# 19_WIFI_BLE.net
KiCad netlist of a schematic drawn in Altium Designer
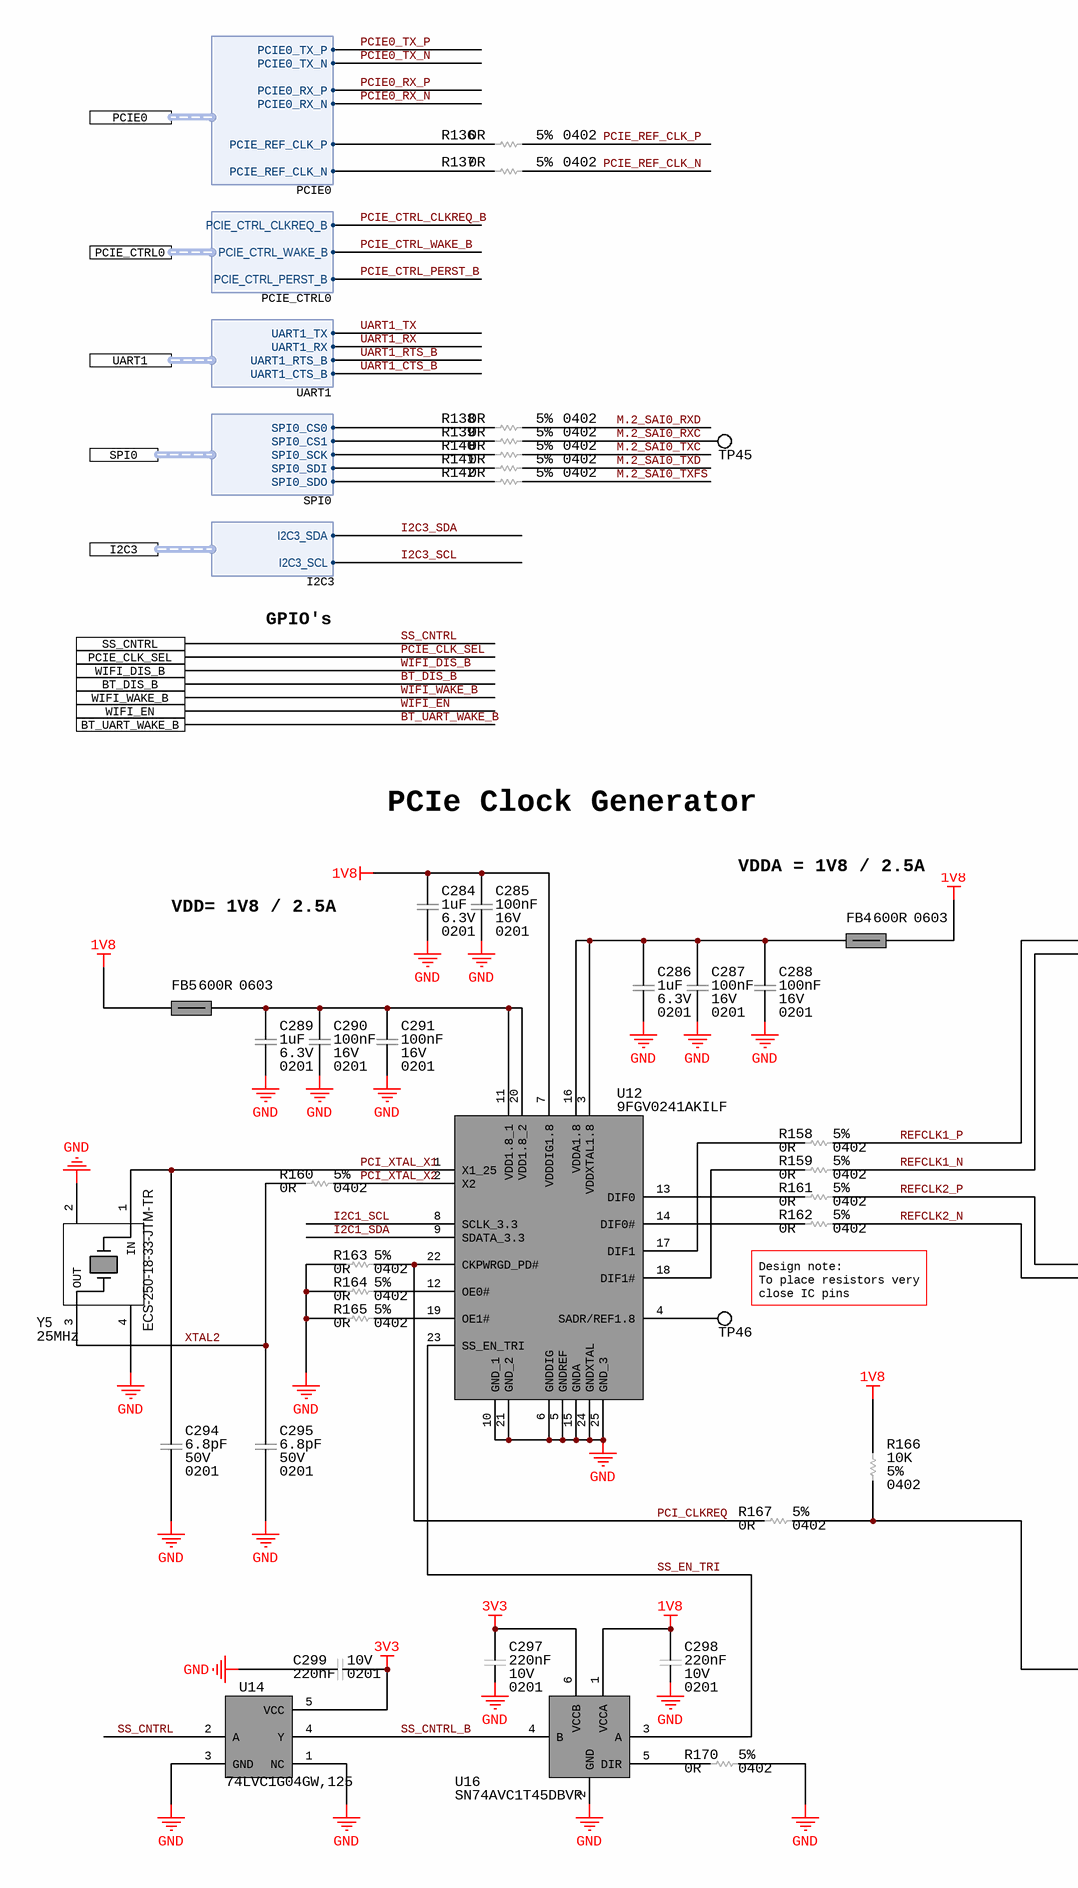
[diagram p0: 19_WIFI_BLE.SchDoc, left]
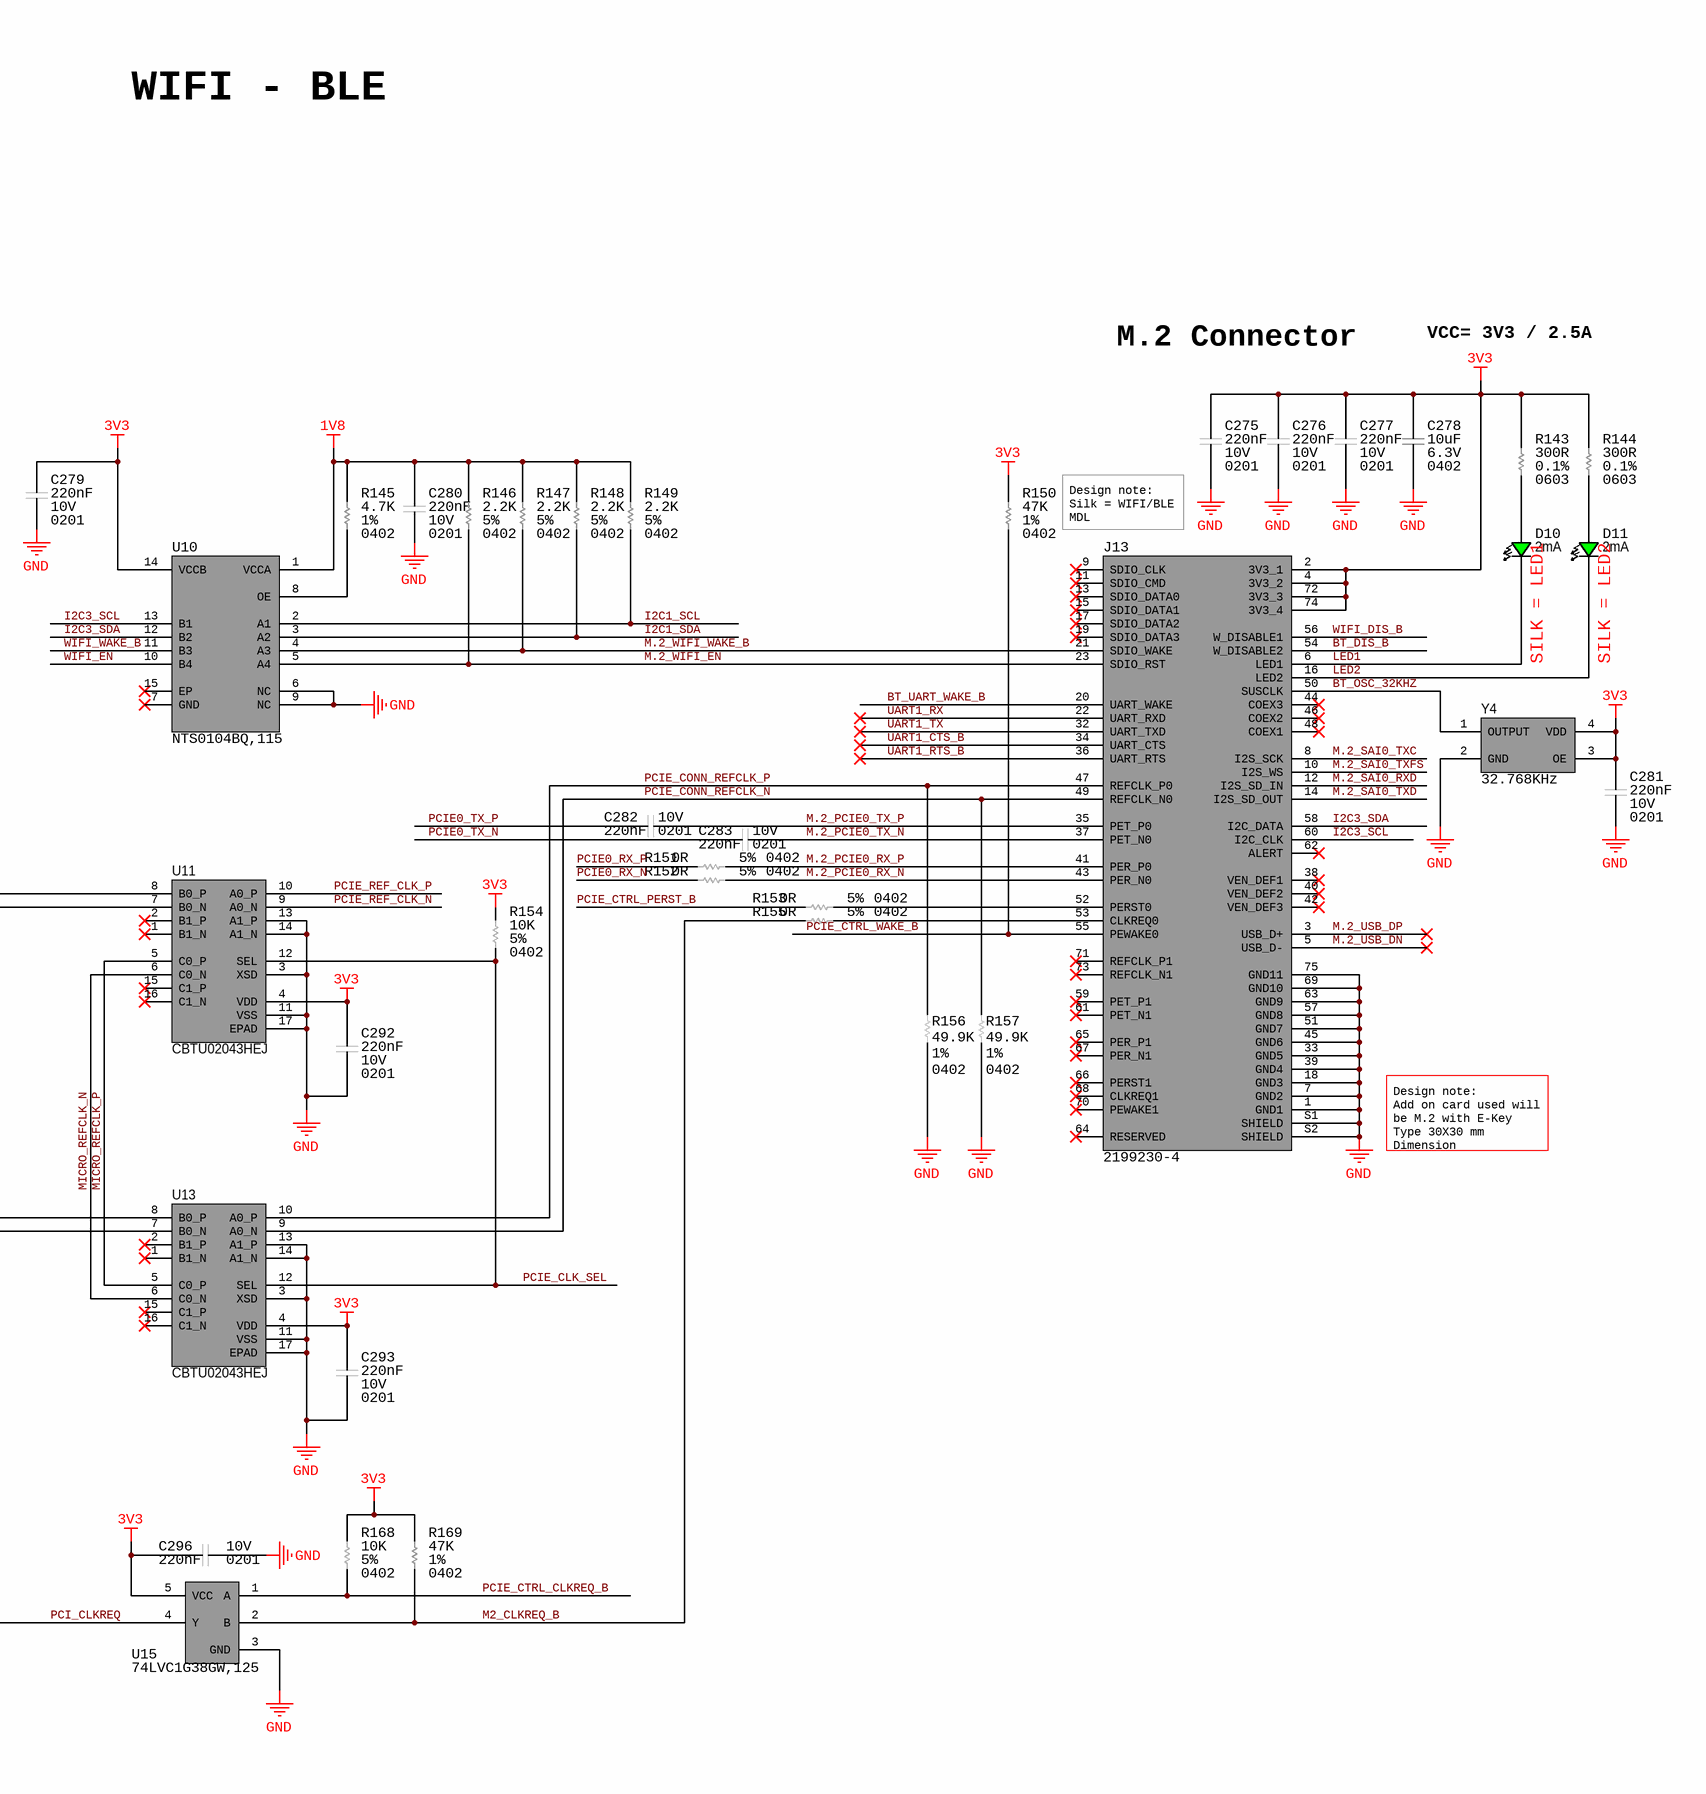
[diagram p1: 19_WIFI_BLE.SchDoc, right]

(export (version "E")
  (design (tool "Eeschema 10.0.6"))
  (components
    (comp (ref "C275")
      (value "LMK063BJ224MP-F")
      (footprint "CAP_0201_CAPC0603X03N")
      (description "Multilayer Ceramic Capacitors (High dielectric type), 10V, 0.22 uF, ± 20 %, 0201, X5R, RoHS")
      (fields
        (field (name "MANUFACTURER") "Taiyo Yuden")
        (field (name "TOLERANCE") "20%")
        (field (name "VOLTAGE RATING (DC)") "10V")
        (field (name "CAPACITANCE") "220nF")
        (field (name "CASE/PACKAGE") "0201")
      )
      (libsource (lib "Electronic Devices_LIB") (part "CAP_0.22UF_10V_X5R_0201"))
    )
    (comp (ref "C276")
      (value "LMK063BJ224MP-F")
      (footprint "CAP_0201_CAPC0603X03N")
      (description "Multilayer Ceramic Capacitors (High dielectric type), 10V, 0.22 uF, ± 20 %, 0201, X5R, RoHS")
      (fields
        (field (name "MANUFACTURER") "Taiyo Yuden")
        (field (name "TOLERANCE") "20%")
        (field (name "VOLTAGE RATING (DC)") "10V")
        (field (name "CAPACITANCE") "220nF")
        (field (name "CASE/PACKAGE") "0201")
      )
      (libsource (lib "Electronic Devices_LIB") (part "CAP_0.22UF_10V_X5R_0201"))
    )
    (comp (ref "C277")
      (value "LMK063BJ224MP-F")
      (footprint "CAP_0201_CAPC0603X03N")
      (description "Multilayer Ceramic Capacitors (High dielectric type), 10V, 0.22 uF, ± 20 %, 0201, X5R, RoHS")
      (fields
        (field (name "MANUFACTURER") "Taiyo Yuden")
        (field (name "TOLERANCE") "20%")
        (field (name "VOLTAGE RATING (DC)") "10V")
        (field (name "CAPACITANCE") "220nF")
        (field (name "CASE/PACKAGE") "0201")
      )
      (libsource (lib "Electronic Devices_LIB") (part "CAP_0.22UF_10V_X5R_0201"))
    )
    (comp (ref "C278")
      (value "CL05A106MQ5NUNC")
      (footprint "CAP_0402_CAPC1005X05N")
      (description "Cap Ceramic 10uF 6.3V X5R 20% SMD 0402 85C T/R")
      (fields
        (field (name "MANUFACTURER") "Samsung")
        (field (name "TOLERANCE") "20%")
        (field (name "CASE/PACKAGE") "0402")
        (field (name "CAPACITANCE") "10uF")
        (field (name "VOLTAGE RATING") "6.3V")
      )
      (libsource (lib "Electronic Devices_LIB") (part "CAP_10UF_6.3V_X5R_0402"))
    )
    (comp (ref "C279")
      (value "LMK063BJ224MP-F")
      (footprint "CAP_0201_CAPC0603X03N")
      (description "Multilayer Ceramic Capacitors (High dielectric type), 10V, 0.22 uF, ± 20 %, 0201, X5R, RoHS")
      (fields
        (field (name "MANUFACTURER") "Taiyo Yuden")
        (field (name "TOLERANCE") "20%")
        (field (name "VOLTAGE RATING (DC)") "10V")
        (field (name "CAPACITANCE") "220nF")
        (field (name "CASE/PACKAGE") "0201")
      )
      (libsource (lib "Electronic Devices_LIB") (part "CAP_0.22UF_10V_X5R_0201"))
    )
    (comp (ref "C280")
      (value "LMK063BJ224MP-F")
      (footprint "CAP_0201_CAPC0603X03N")
      (description "Multilayer Ceramic Capacitors (High dielectric type), 10V, 0.22 uF, ± 20 %, 0201, X5R, RoHS")
      (fields
        (field (name "MANUFACTURER") "Taiyo Yuden")
        (field (name "TOLERANCE") "20%")
        (field (name "VOLTAGE RATING (DC)") "10V")
        (field (name "CAPACITANCE") "220nF")
        (field (name "CASE/PACKAGE") "0201")
      )
      (libsource (lib "Electronic Devices_LIB") (part "CAP_0.22UF_10V_X5R_0201"))
    )
    (comp (ref "C281")
      (value "LMK063BJ224MP-F")
      (footprint "CAP_0201_CAPC0603X03N")
      (description "Multilayer Ceramic Capacitors (High dielectric type), 10V, 0.22 uF, ± 20 %, 0201, X5R, RoHS")
      (fields
        (field (name "MANUFACTURER") "Taiyo Yuden")
        (field (name "TOLERANCE") "20%")
        (field (name "VOLTAGE RATING (DC)") "10V")
        (field (name "CAPACITANCE") "220nF")
        (field (name "CASE/PACKAGE") "0201")
      )
      (libsource (lib "Electronic Devices_LIB") (part "CAP_0.22UF_10V_X5R_0201"))
    )
    (comp (ref "C282")
      (value "LMK063BJ224MP-F")
      (footprint "CAP_0201_CAPC0603X03N")
      (description "Multilayer Ceramic Capacitors (High dielectric type), 10V, 0.22 uF, ± 20 %, 0201, X5R, RoHS")
      (fields
        (field (name "MANUFACTURER") "Taiyo Yuden")
        (field (name "TOLERANCE") "20%")
        (field (name "VOLTAGE RATING (DC)") "10V")
        (field (name "CAPACITANCE") "220nF")
        (field (name "CASE/PACKAGE") "0201")
      )
      (libsource (lib "Electronic Devices_LIB") (part "CAP_0.22UF_10V_X5R_0201"))
    )
    (comp (ref "C283")
      (value "LMK063BJ224MP-F")
      (footprint "CAP_0201_CAPC0603X03N")
      (description "Multilayer Ceramic Capacitors (High dielectric type), 10V, 0.22 uF, ± 20 %, 0201, X5R, RoHS")
      (fields
        (field (name "MANUFACTURER") "Taiyo Yuden")
        (field (name "TOLERANCE") "20%")
        (field (name "VOLTAGE RATING (DC)") "10V")
        (field (name "CAPACITANCE") "220nF")
        (field (name "CASE/PACKAGE") "0201")
      )
      (libsource (lib "Electronic Devices_LIB") (part "CAP_0.22UF_10V_X5R_0201"))
    )
    (comp (ref "C284")
      (value "02016D105MAT2A")
      (footprint "CAP_0201_CAPC0603X03N")
      (description "0201 1 uF 6.3 V ±20 % Tolerance X5R Surface Mount Multilayer Ceramic Capacitor")
      (fields
        (field (name "MANUFACTURER") "Kyocera AVX")
        (field (name "TOLERANCE") "20%")
        (field (name "VOLTAGE RATING (DC)") "6.3V")
        (field (name "CAPACITANCE") "1uF")
        (field (name "CASE/PACKAGE") "0201")
      )
      (libsource (lib "Electronic Devices_LIB") (part "CAP_1UF_6.3V_X5R_0201"))
    )
    (comp (ref "C285")
      (value "GRM033C71C104KE14D")
      (footprint "CAP_0201_CAPC0603X03N")
      (description "Multilayer Ceramic Capacitor, 0.1 uF, 16 V, ± 10%, X7S, 0201 [0603 Metric]")
      (fields
        (field (name "MANUFACTURER") "Murata")
        (field (name "TOLERANCE") "10%")
        (field (name "VOLTAGE RATING") "16V")
        (field (name "CAPACITANCE") "100nF")
        (field (name "CASE/PACKAGE") "0201")
      )
      (libsource (lib "Electronic Devices_LIB") (part "CAP_100nF_16V_X7S_0201"))
    )
    (comp (ref "C286")
      (value "02016D105MAT2A")
      (footprint "CAP_0201_CAPC0603X03N")
      (description "0201 1 uF 6.3 V ±20 % Tolerance X5R Surface Mount Multilayer Ceramic Capacitor")
      (fields
        (field (name "MANUFACTURER") "Kyocera AVX")
        (field (name "TOLERANCE") "20%")
        (field (name "VOLTAGE RATING (DC)") "6.3V")
        (field (name "CAPACITANCE") "1uF")
        (field (name "CASE/PACKAGE") "0201")
      )
      (libsource (lib "Electronic Devices_LIB") (part "CAP_1UF_6.3V_X5R_0201"))
    )
    (comp (ref "C287")
      (value "GRM033C71C104KE14D")
      (footprint "CAP_0201_CAPC0603X03N")
      (description "Multilayer Ceramic Capacitor, 0.1 uF, 16 V, ± 10%, X7S, 0201 [0603 Metric]")
      (fields
        (field (name "MANUFACTURER") "Murata")
        (field (name "TOLERANCE") "10%")
        (field (name "VOLTAGE RATING") "16V")
        (field (name "CAPACITANCE") "100nF")
        (field (name "CASE/PACKAGE") "0201")
      )
      (libsource (lib "Electronic Devices_LIB") (part "CAP_100nF_16V_X7S_0201"))
    )
    (comp (ref "C288")
      (value "GRM033C71C104KE14D")
      (footprint "CAP_0201_CAPC0603X03N")
      (description "Multilayer Ceramic Capacitor, 0.1 uF, 16 V, ± 10%, X7S, 0201 [0603 Metric]")
      (fields
        (field (name "MANUFACTURER") "Murata")
        (field (name "TOLERANCE") "10%")
        (field (name "VOLTAGE RATING") "16V")
        (field (name "CAPACITANCE") "100nF")
        (field (name "CASE/PACKAGE") "0201")
      )
      (libsource (lib "Electronic Devices_LIB") (part "CAP_100nF_16V_X7S_0201"))
    )
    (comp (ref "C289")
      (value "02016D105MAT2A")
      (footprint "CAP_0201_CAPC0603X03N")
      (description "0201 1 uF 6.3 V ±20 % Tolerance X5R Surface Mount Multilayer Ceramic Capacitor")
      (fields
        (field (name "MANUFACTURER") "Kyocera AVX")
        (field (name "TOLERANCE") "20%")
        (field (name "VOLTAGE RATING (DC)") "6.3V")
        (field (name "CAPACITANCE") "1uF")
        (field (name "CASE/PACKAGE") "0201")
      )
      (libsource (lib "Electronic Devices_LIB") (part "CAP_1UF_6.3V_X5R_0201"))
    )
    (comp (ref "C290")
      (value "GRM033C71C104KE14D")
      (footprint "CAP_0201_CAPC0603X03N")
      (description "Multilayer Ceramic Capacitor, 0.1 uF, 16 V, ± 10%, X7S, 0201 [0603 Metric]")
      (fields
        (field (name "MANUFACTURER") "Murata")
        (field (name "TOLERANCE") "10%")
        (field (name "VOLTAGE RATING") "16V")
        (field (name "CAPACITANCE") "100nF")
        (field (name "CASE/PACKAGE") "0201")
      )
      (libsource (lib "Electronic Devices_LIB") (part "CAP_100nF_16V_X7S_0201"))
    )
    (comp (ref "C291")
      (value "GRM033C71C104KE14D")
      (footprint "CAP_0201_CAPC0603X03N")
      (description "Multilayer Ceramic Capacitor, 0.1 uF, 16 V, ± 10%, X7S, 0201 [0603 Metric]")
      (fields
        (field (name "MANUFACTURER") "Murata")
        (field (name "TOLERANCE") "10%")
        (field (name "VOLTAGE RATING") "16V")
        (field (name "CAPACITANCE") "100nF")
        (field (name "CASE/PACKAGE") "0201")
      )
      (libsource (lib "Electronic Devices_LIB") (part "CAP_100nF_16V_X7S_0201"))
    )
    (comp (ref "C292")
      (value "LMK063BJ224MP-F")
      (footprint "CAP_0201_CAPC0603X03N")
      (description "Multilayer Ceramic Capacitors (High dielectric type), 10V, 0.22 uF, ± 20 %, 0201, X5R, RoHS")
      (fields
        (field (name "MANUFACTURER") "Taiyo Yuden")
        (field (name "TOLERANCE") "20%")
        (field (name "VOLTAGE RATING (DC)") "10V")
        (field (name "CAPACITANCE") "220nF")
        (field (name "CASE/PACKAGE") "0201")
      )
      (libsource (lib "Electronic Devices_LIB") (part "CAP_0.22UF_10V_X5R_0201"))
    )
    (comp (ref "C293")
      (value "LMK063BJ224MP-F")
      (footprint "CAP_0201_CAPC0603X03N")
      (description "Multilayer Ceramic Capacitors (High dielectric type), 10V, 0.22 uF, ± 20 %, 0201, X5R, RoHS")
      (fields
        (field (name "MANUFACTURER") "Taiyo Yuden")
        (field (name "TOLERANCE") "20%")
        (field (name "VOLTAGE RATING (DC)") "10V")
        (field (name "CAPACITANCE") "220nF")
        (field (name "CASE/PACKAGE") "0201")
      )
      (libsource (lib "Electronic Devices_LIB") (part "CAP_0.22UF_10V_X5R_0201"))
    )
    (comp (ref "C294")
      (value "GRM0335C1H6R8BA01D")
      (footprint "CAP_0201_CAPC0603X03N")
      (description "Cap Ceramic 6.8pF 50V C0G 0.1pF Pad SMD 0201 125C T/R")
      (fields
        (field (name "MANUFACTURER") "Murata")
        (field (name "CAPACITANCE") "6.8pF")
        (field (name "VOLTAGE RATING") "50V")
        (field (name "CASE/PACKAGE") "0201")
      )
      (libsource (lib "Electronic Devices_LIB") (part "CAP_6.8pF_50V_NP0_0201"))
    )
    (comp (ref "C295")
      (value "GRM0335C1H6R8BA01D")
      (footprint "CAP_0201_CAPC0603X03N")
      (description "Cap Ceramic 6.8pF 50V C0G 0.1pF Pad SMD 0201 125C T/R")
      (fields
        (field (name "MANUFACTURER") "Murata")
        (field (name "CAPACITANCE") "6.8pF")
        (field (name "VOLTAGE RATING") "50V")
        (field (name "CASE/PACKAGE") "0201")
      )
      (libsource (lib "Electronic Devices_LIB") (part "CAP_6.8pF_50V_NP0_0201"))
    )
    (comp (ref "C296")
      (value "LMK063BJ224MP-F")
      (footprint "CAP_0201_CAPC0603X03N")
      (description "Multilayer Ceramic Capacitors (High dielectric type), 10V, 0.22 uF, ± 20 %, 0201, X5R, RoHS")
      (fields
        (field (name "MANUFACTURER") "Taiyo Yuden")
        (field (name "TOLERANCE") "20%")
        (field (name "VOLTAGE RATING (DC)") "10V")
        (field (name "CAPACITANCE") "220nF")
        (field (name "CASE/PACKAGE") "0201")
      )
      (libsource (lib "Electronic Devices_LIB") (part "CAP_0.22UF_10V_X5R_0201"))
    )
    (comp (ref "C297")
      (value "LMK063BJ224MP-F")
      (footprint "CAP_0201_CAPC0603X03N")
      (description "Multilayer Ceramic Capacitors (High dielectric type), 10V, 0.22 uF, ± 20 %, 0201, X5R, RoHS")
      (fields
        (field (name "MANUFACTURER") "Taiyo Yuden")
        (field (name "TOLERANCE") "20%")
        (field (name "VOLTAGE RATING (DC)") "10V")
        (field (name "CAPACITANCE") "220nF")
        (field (name "CASE/PACKAGE") "0201")
      )
      (libsource (lib "Electronic Devices_LIB") (part "CAP_0.22UF_10V_X5R_0201"))
    )
    (comp (ref "C298")
      (value "LMK063BJ224MP-F")
      (footprint "CAP_0201_CAPC0603X03N")
      (description "Multilayer Ceramic Capacitors (High dielectric type), 10V, 0.22 uF, ± 20 %, 0201, X5R, RoHS")
      (fields
        (field (name "MANUFACTURER") "Taiyo Yuden")
        (field (name "TOLERANCE") "20%")
        (field (name "VOLTAGE RATING (DC)") "10V")
        (field (name "CAPACITANCE") "220nF")
        (field (name "CASE/PACKAGE") "0201")
      )
      (libsource (lib "Electronic Devices_LIB") (part "CAP_0.22UF_10V_X5R_0201"))
    )
    (comp (ref "C299")
      (value "LMK063BJ224MP-F")
      (footprint "CAP_0201_CAPC0603X03N")
      (description "Multilayer Ceramic Capacitors (High dielectric type), 10V, 0.22 uF, ± 20 %, 0201, X5R, RoHS")
      (fields
        (field (name "MANUFACTURER") "Taiyo Yuden")
        (field (name "TOLERANCE") "20%")
        (field (name "VOLTAGE RATING (DC)") "10V")
        (field (name "CAPACITANCE") "220nF")
        (field (name "CASE/PACKAGE") "0201")
      )
      (libsource (lib "Electronic Devices_LIB") (part "CAP_0.22UF_10V_X5R_0201"))
    )
    (comp (ref "D10")
      (value "APDA3020LZGCK")
      (footprint "LED_GREEN_APDA3020LZGCK")
      (description "LED GREEN CLEAR 2SMD R/A  1500mcd")
      (fields (field (name "MANUFACTURER") "Kingbright") (field (name "TEST CURRENT") "2mA"))
      (libsource (lib "Electronic Devices_LIB") (part "LED_DIO_GREEN_2mA_APDA3020LZGCK"))
    )
    (comp (ref "D11")
      (value "APDA3020LZGCK")
      (footprint "LED_GREEN_APDA3020LZGCK")
      (description "LED GREEN CLEAR 2SMD R/A  1500mcd")
      (fields (field (name "MANUFACTURER") "Kingbright") (field (name "TEST CURRENT") "2mA"))
      (libsource (lib "Electronic Devices_LIB") (part "LED_DIO_GREEN_2mA_APDA3020LZGCK"))
    )
    (comp (ref "FB4")
      (value "742792653")
      (footprint "IND_0603_INDC1608X08N")
      (description "Chip NTC Thermistors (Sensor), Resistance (at 25°C)=10kΩ, Resistance Tolerance (at 25°C)=±1%")
      (fields
        (field (name "MANUFACTURER") "Wurth Electronics")
        (field (name "TOLERANCE") "25%")
        (field (name "IMPEDANCE") "600R")
        (field (name "CASE CODE (IMPERIAL)") "0603")
      )
      (libsource (lib "Electronic Devices_LIB") (part "IND_FERRITE_BEADS_600R_300mA_0603_742792653"))
    )
    (comp (ref "FB5")
      (value "742792653")
      (footprint "IND_0603_INDC1608X08N")
      (description "Chip NTC Thermistors (Sensor), Resistance (at 25°C)=10kΩ, Resistance Tolerance (at 25°C)=±1%")
      (fields
        (field (name "MANUFACTURER") "Wurth Electronics")
        (field (name "TOLERANCE") "25%")
        (field (name "IMPEDANCE") "600R")
        (field (name "CASE CODE (IMPERIAL)") "0603")
      )
      (libsource (lib "Electronic Devices_LIB") (part "IND_FERRITE_BEADS_600R_300mA_0603_742792653"))
    )
    (comp (ref "J13")
      (value "2199230-4")
      (footprint "TE_21992304")
      (description "CONNECTOR, BACKPLANE, HOUSING, RCPT, 67POS, 2ROW; Connector Type: Card Edge; Seri")
      (fields (field (name "MANUFACTURER") "TE Connectivity"))
      (libsource (lib "Electronic Devices_LIB") (part "CONN_M.2_FEMALE_2199230-4"))
    )
    (comp (ref "R136")
      (value "ERJ-2GE0R00X")
      (footprint "RES_0402_RESC1005X04N")
      (description "SMD Chip Resistor, Jumper, 0 ohm, 100 mW, 0402 [1005 Metric], Thick Film, General Purpose")
      (fields
        (field (name "MANUFACTURER") "Panasonic")
        (field (name "CASE CODE (IMPERIAL)") "0402")
        (field (name "TOLERANCE") "5%")
        (field (name "RESISTANCE") "0R")
      )
      (libsource (lib "Electronic Devices_LIB") (part "RES_0R_5%_100mW_0402"))
    )
    (comp (ref "R137")
      (value "ERJ-2GE0R00X")
      (footprint "RES_0402_RESC1005X04N")
      (description "SMD Chip Resistor, Jumper, 0 ohm, 100 mW, 0402 [1005 Metric], Thick Film, General Purpose")
      (fields
        (field (name "MANUFACTURER") "Panasonic")
        (field (name "CASE CODE (IMPERIAL)") "0402")
        (field (name "TOLERANCE") "5%")
        (field (name "RESISTANCE") "0R")
      )
      (libsource (lib "Electronic Devices_LIB") (part "RES_0R_5%_100mW_0402"))
    )
    (comp (ref "R138")
      (value "ERJ-2GE0R00X")
      (footprint "RES_0402_RESC1005X04N")
      (description "SMD Chip Resistor, Jumper, 0 ohm, 100 mW, 0402 [1005 Metric], Thick Film, General Purpose")
      (fields
        (field (name "MANUFACTURER") "Panasonic")
        (field (name "CASE CODE (IMPERIAL)") "0402")
        (field (name "TOLERANCE") "5%")
        (field (name "RESISTANCE") "0R")
      )
      (libsource (lib "Electronic Devices_LIB") (part "RES_0R_5%_100mW_0402"))
    )
    (comp (ref "R139")
      (value "ERJ-2GE0R00X")
      (footprint "RES_0402_RESC1005X04N")
      (description "SMD Chip Resistor, Jumper, 0 ohm, 100 mW, 0402 [1005 Metric], Thick Film, General Purpose")
      (fields
        (field (name "MANUFACTURER") "Panasonic")
        (field (name "CASE CODE (IMPERIAL)") "0402")
        (field (name "TOLERANCE") "5%")
        (field (name "RESISTANCE") "0R")
      )
      (libsource (lib "Electronic Devices_LIB") (part "RES_0R_5%_100mW_0402"))
    )
    (comp (ref "R140")
      (value "ERJ-2GE0R00X")
      (footprint "RES_0402_RESC1005X04N")
      (description "SMD Chip Resistor, Jumper, 0 ohm, 100 mW, 0402 [1005 Metric], Thick Film, General Purpose")
      (fields
        (field (name "MANUFACTURER") "Panasonic")
        (field (name "CASE CODE (IMPERIAL)") "0402")
        (field (name "TOLERANCE") "5%")
        (field (name "RESISTANCE") "0R")
      )
      (libsource (lib "Electronic Devices_LIB") (part "RES_0R_5%_100mW_0402"))
    )
    (comp (ref "R141")
      (value "ERJ-2GE0R00X")
      (footprint "RES_0402_RESC1005X04N")
      (description "SMD Chip Resistor, Jumper, 0 ohm, 100 mW, 0402 [1005 Metric], Thick Film, General Purpose")
      (fields
        (field (name "MANUFACTURER") "Panasonic")
        (field (name "CASE CODE (IMPERIAL)") "0402")
        (field (name "TOLERANCE") "5%")
        (field (name "RESISTANCE") "0R")
      )
      (libsource (lib "Electronic Devices_LIB") (part "RES_0R_5%_100mW_0402"))
    )
    (comp (ref "R142")
      (value "ERJ-2GE0R00X")
      (footprint "RES_0402_RESC1005X04N")
      (description "SMD Chip Resistor, Jumper, 0 ohm, 100 mW, 0402 [1005 Metric], Thick Film, General Purpose")
      (fields
        (field (name "MANUFACTURER") "Panasonic")
        (field (name "CASE CODE (IMPERIAL)") "0402")
        (field (name "TOLERANCE") "5%")
        (field (name "RESISTANCE") "0R")
      )
      (libsource (lib "Electronic Devices_LIB") (part "RES_0R_5%_100mW_0402"))
    )
    (comp (ref "R143")
      (value "RT0603BRD07300RL")
      (footprint "RES_0603_RESC1608X04N")
      (description "Res Thin Film 0603 300 Ohm 0.1% 0.1W(1/10W) ±25ppm/C Pad SMD T/R")
      (fields
        (field (name "MANUFACTURER") "Yageo")
        (field (name "CASE CODE (IMPERIAL)") "0603")
        (field (name "TOLERANCE") "0.1%")
        (field (name "RESISTANCE") "300R")
      )
      (libsource (lib "Electronic Devices_LIB") (part "RES_300R_0.1%_100mW_0603"))
    )
    (comp (ref "R144")
      (value "RT0603BRD07300RL")
      (footprint "RES_0603_RESC1608X04N")
      (description "Res Thin Film 0603 300 Ohm 0.1% 0.1W(1/10W) ±25ppm/C Pad SMD T/R")
      (fields
        (field (name "MANUFACTURER") "Yageo")
        (field (name "CASE CODE (IMPERIAL)") "0603")
        (field (name "TOLERANCE") "0.1%")
        (field (name "RESISTANCE") "300R")
      )
      (libsource (lib "Electronic Devices_LIB") (part "RES_300R_0.1%_100mW_0603"))
    )
    (comp (ref "R145")
      (value "ERJ-2RKF4701X")
      (footprint "RES_0402_RESC1005X04N")
      (description "Res Thick Film 0402 4.7K Ohm 1% 0.1W ±100ppm/°C Molded SMD Punched Carrier T/R")
      (fields
        (field (name "MANUFACTURER") "Panasonic")
        (field (name "TOLERANCE") "1%")
        (field (name "CASE CODE (IMPERIAL)") "0402")
        (field (name "RESISTANCE") "4.7K")
      )
      (libsource (lib "Electronic Devices_LIB") (part "RES_4.7K_1%_100mW_0402"))
    )
    (comp (ref "R146")
      (value "RC0402JR-072K2L")
      (footprint "RES_0402_RESC1005X04N")
      (description "SMD Chip Resistor, 2.2 kOhm, ± 5%, 63 mW, 0402 [1005 Metric], Thick Film, General Purpose")
      (fields
        (field (name "MANUFACTURER") "Yageo")
        (field (name "TOLERANCE") "5%")
        (field (name "RESISTANCE") "2.2K")
        (field (name "CASE/PACKAGE") "0402")
      )
      (libsource (lib "Electronic Devices_LIB") (part "RES_2.2K_5%_63mW_0402"))
    )
    (comp (ref "R147")
      (value "RC0402JR-072K2L")
      (footprint "RES_0402_RESC1005X04N")
      (description "SMD Chip Resistor, 2.2 kOhm, ± 5%, 63 mW, 0402 [1005 Metric], Thick Film, General Purpose")
      (fields
        (field (name "MANUFACTURER") "Yageo")
        (field (name "TOLERANCE") "5%")
        (field (name "RESISTANCE") "2.2K")
        (field (name "CASE/PACKAGE") "0402")
      )
      (libsource (lib "Electronic Devices_LIB") (part "RES_2.2K_5%_63mW_0402"))
    )
    (comp (ref "R148")
      (value "RC0402JR-072K2L")
      (footprint "RES_0402_RESC1005X04N")
      (description "SMD Chip Resistor, 2.2 kOhm, ± 5%, 63 mW, 0402 [1005 Metric], Thick Film, General Purpose")
      (fields
        (field (name "MANUFACTURER") "Yageo")
        (field (name "TOLERANCE") "5%")
        (field (name "RESISTANCE") "2.2K")
        (field (name "CASE/PACKAGE") "0402")
      )
      (libsource (lib "Electronic Devices_LIB") (part "RES_2.2K_5%_63mW_0402"))
    )
    (comp (ref "R149")
      (value "RC0402JR-072K2L")
      (footprint "RES_0402_RESC1005X04N")
      (description "SMD Chip Resistor, 2.2 kOhm, ± 5%, 63 mW, 0402 [1005 Metric], Thick Film, General Purpose")
      (fields
        (field (name "MANUFACTURER") "Yageo")
        (field (name "TOLERANCE") "5%")
        (field (name "RESISTANCE") "2.2K")
        (field (name "CASE/PACKAGE") "0402")
      )
      (libsource (lib "Electronic Devices_LIB") (part "RES_2.2K_5%_63mW_0402"))
    )
    (comp (ref "R150")
      (value "ERJ-2RKF4702X")
      (footprint "RES_0402_RESC1005X04N")
      (description "Res Thick Film 0402 47K Ohm 1% 0.1W ±100ppm/°C Molded SMD Punched Carrier T/R")
      (fields
        (field (name "MANUFACTURER") "Panasonic")
        (field (name "TOLERANCE") "1%")
        (field (name "RESISTANCE") "47K")
        (field (name "CASE/PACKAGE") "0402")
      )
      (libsource (lib "Electronic Devices_LIB") (part "RES_47K_1%_100MW_0402"))
    )
    (comp (ref "R151")
      (value "ERJ-2GE0R00X")
      (footprint "RES_0402_RESC1005X04N")
      (description "SMD Chip Resistor, Jumper, 0 ohm, 100 mW, 0402 [1005 Metric], Thick Film, General Purpose")
      (fields
        (field (name "MANUFACTURER") "Panasonic")
        (field (name "CASE CODE (IMPERIAL)") "0402")
        (field (name "TOLERANCE") "5%")
        (field (name "RESISTANCE") "0R")
      )
      (libsource (lib "Electronic Devices_LIB") (part "RES_0R_5%_100mW_0402"))
    )
    (comp (ref "R152")
      (value "ERJ-2GE0R00X")
      (footprint "RES_0402_RESC1005X04N")
      (description "SMD Chip Resistor, Jumper, 0 ohm, 100 mW, 0402 [1005 Metric], Thick Film, General Purpose")
      (fields
        (field (name "MANUFACTURER") "Panasonic")
        (field (name "CASE CODE (IMPERIAL)") "0402")
        (field (name "TOLERANCE") "5%")
        (field (name "RESISTANCE") "0R")
      )
      (libsource (lib "Electronic Devices_LIB") (part "RES_0R_5%_100mW_0402"))
    )
    (comp (ref "R153")
      (value "ERJ-2GE0R00X")
      (footprint "RES_0402_RESC1005X04N")
      (description "SMD Chip Resistor, Jumper, 0 ohm, 100 mW, 0402 [1005 Metric], Thick Film, General Purpose")
      (fields
        (field (name "MANUFACTURER") "Panasonic")
        (field (name "CASE CODE (IMPERIAL)") "0402")
        (field (name "TOLERANCE") "5%")
        (field (name "RESISTANCE") "0R")
      )
      (libsource (lib "Electronic Devices_LIB") (part "RES_0R_5%_100mW_0402"))
    )
    (comp (ref "R154")
      (value "ERJ-2GEJ103X")
      (footprint "RES_0402_RESC1005X04N")
      (description "Res Thick Film 0402 10K Ohm 5% 1/10W ±200ppm/°C Molded SMD Punched Carrier T/R")
      (fields
        (field (name "MANUFACTURER") "Panasonic")
        (field (name "TOLERANCE") "5%")
        (field (name "RESISTANCE") "10K")
        (field (name "CASE/PACKAGE") "0402")
      )
      (libsource (lib "Electronic Devices_LIB") (part "RES_10K_5%_100mW_0402"))
    )
    (comp (ref "R155")
      (value "ERJ-2GE0R00X")
      (footprint "RES_0402_RESC1005X04N")
      (description "SMD Chip Resistor, Jumper, 0 ohm, 100 mW, 0402 [1005 Metric], Thick Film, General Purpose")
      (fields
        (field (name "MANUFACTURER") "Panasonic")
        (field (name "CASE CODE (IMPERIAL)") "0402")
        (field (name "TOLERANCE") "5%")
        (field (name "RESISTANCE") "0R")
      )
      (libsource (lib "Electronic Devices_LIB") (part "RES_0R_5%_100mW_0402"))
    )
    (comp (ref "R156")
      (value "CRCW040249K9FKED")
      (footprint "RES_0402_RESC1005X04N")
      (description "Res Thick Film 0402 49.9K Ohm 1% 1/16W ±100ppm/°C Molded SMD SMD Paper T/R")
      (fields
        (field (name "MANUFACTURER") "Vishay")
        (field (name "RESISTANCE") "49.9K")
        (field (name "TOLERANCE") "1%")
        (field (name "CASE/PACKAGE") "0402")
      )
      (libsource (lib "Electronic Devices_LIB") (part "RES_49.9K_1%_0.0625W_0402"))
    )
    (comp (ref "R157")
      (value "CRCW040249K9FKED")
      (footprint "RES_0402_RESC1005X04N")
      (description "Res Thick Film 0402 49.9K Ohm 1% 1/16W ±100ppm/°C Molded SMD SMD Paper T/R")
      (fields
        (field (name "MANUFACTURER") "Vishay")
        (field (name "RESISTANCE") "49.9K")
        (field (name "TOLERANCE") "1%")
        (field (name "CASE/PACKAGE") "0402")
      )
      (libsource (lib "Electronic Devices_LIB") (part "RES_49.9K_1%_0.0625W_0402"))
    )
    (comp (ref "R158")
      (value "ERJ-2GE0R00X")
      (footprint "RES_0402_RESC1005X04N")
      (description "SMD Chip Resistor, Jumper, 0 ohm, 100 mW, 0402 [1005 Metric], Thick Film, General Purpose")
      (fields
        (field (name "MANUFACTURER") "Panasonic")
        (field (name "CASE CODE (IMPERIAL)") "0402")
        (field (name "TOLERANCE") "5%")
        (field (name "RESISTANCE") "0R")
      )
      (libsource (lib "Electronic Devices_LIB") (part "RES_0R_5%_100mW_0402"))
    )
    (comp (ref "R159")
      (value "ERJ-2GE0R00X")
      (footprint "RES_0402_RESC1005X04N")
      (description "SMD Chip Resistor, Jumper, 0 ohm, 100 mW, 0402 [1005 Metric], Thick Film, General Purpose")
      (fields
        (field (name "MANUFACTURER") "Panasonic")
        (field (name "CASE CODE (IMPERIAL)") "0402")
        (field (name "TOLERANCE") "5%")
        (field (name "RESISTANCE") "0R")
      )
      (libsource (lib "Electronic Devices_LIB") (part "RES_0R_5%_100mW_0402"))
    )
    (comp (ref "R160")
      (value "ERJ-2GE0R00X")
      (footprint "RES_0402_RESC1005X04N")
      (description "SMD Chip Resistor, Jumper, 0 ohm, 100 mW, 0402 [1005 Metric], Thick Film, General Purpose")
      (fields
        (field (name "MANUFACTURER") "Panasonic")
        (field (name "CASE CODE (IMPERIAL)") "0402")
        (field (name "TOLERANCE") "5%")
        (field (name "RESISTANCE") "0R")
      )
      (libsource (lib "Electronic Devices_LIB") (part "RES_0R_5%_100mW_0402"))
    )
    (comp (ref "R161")
      (value "ERJ-2GE0R00X")
      (footprint "RES_0402_RESC1005X04N")
      (description "SMD Chip Resistor, Jumper, 0 ohm, 100 mW, 0402 [1005 Metric], Thick Film, General Purpose")
      (fields
        (field (name "MANUFACTURER") "Panasonic")
        (field (name "CASE CODE (IMPERIAL)") "0402")
        (field (name "TOLERANCE") "5%")
        (field (name "RESISTANCE") "0R")
      )
      (libsource (lib "Electronic Devices_LIB") (part "RES_0R_5%_100mW_0402"))
    )
    (comp (ref "R162")
      (value "ERJ-2GE0R00X")
      (footprint "RES_0402_RESC1005X04N")
      (description "SMD Chip Resistor, Jumper, 0 ohm, 100 mW, 0402 [1005 Metric], Thick Film, General Purpose")
      (fields
        (field (name "MANUFACTURER") "Panasonic")
        (field (name "CASE CODE (IMPERIAL)") "0402")
        (field (name "TOLERANCE") "5%")
        (field (name "RESISTANCE") "0R")
      )
      (libsource (lib "Electronic Devices_LIB") (part "RES_0R_5%_100mW_0402"))
    )
    (comp (ref "R163")
      (value "ERJ-2GE0R00X")
      (footprint "RES_0402_RESC1005X04N")
      (description "SMD Chip Resistor, Jumper, 0 ohm, 100 mW, 0402 [1005 Metric], Thick Film, General Purpose")
      (fields
        (field (name "MANUFACTURER") "Panasonic")
        (field (name "CASE CODE (IMPERIAL)") "0402")
        (field (name "TOLERANCE") "5%")
        (field (name "RESISTANCE") "0R")
      )
      (libsource (lib "Electronic Devices_LIB") (part "RES_0R_5%_100mW_0402"))
    )
    (comp (ref "R164")
      (value "ERJ-2GE0R00X")
      (footprint "RES_0402_RESC1005X04N")
      (description "SMD Chip Resistor, Jumper, 0 ohm, 100 mW, 0402 [1005 Metric], Thick Film, General Purpose")
      (fields
        (field (name "MANUFACTURER") "Panasonic")
        (field (name "CASE CODE (IMPERIAL)") "0402")
        (field (name "TOLERANCE") "5%")
        (field (name "RESISTANCE") "0R")
      )
      (libsource (lib "Electronic Devices_LIB") (part "RES_0R_5%_100mW_0402"))
    )
    (comp (ref "R165")
      (value "ERJ-2GE0R00X")
      (footprint "RES_0402_RESC1005X04N")
      (description "SMD Chip Resistor, Jumper, 0 ohm, 100 mW, 0402 [1005 Metric], Thick Film, General Purpose")
      (fields
        (field (name "MANUFACTURER") "Panasonic")
        (field (name "CASE CODE (IMPERIAL)") "0402")
        (field (name "TOLERANCE") "5%")
        (field (name "RESISTANCE") "0R")
      )
      (libsource (lib "Electronic Devices_LIB") (part "RES_0R_5%_100mW_0402"))
    )
    (comp (ref "R166")
      (value "ERJ-2GEJ103X")
      (footprint "RES_0402_RESC1005X04N")
      (description "Res Thick Film 0402 10K Ohm 5% 1/10W ±200ppm/°C Molded SMD Punched Carrier T/R")
      (fields
        (field (name "MANUFACTURER") "Panasonic")
        (field (name "TOLERANCE") "5%")
        (field (name "RESISTANCE") "10K")
        (field (name "CASE/PACKAGE") "0402")
      )
      (libsource (lib "Electronic Devices_LIB") (part "RES_10K_5%_100mW_0402"))
    )
    (comp (ref "R167")
      (value "ERJ-2GE0R00X")
      (footprint "RES_0402_RESC1005X04N")
      (description "SMD Chip Resistor, Jumper, 0 ohm, 100 mW, 0402 [1005 Metric], Thick Film, General Purpose")
      (fields
        (field (name "MANUFACTURER") "Panasonic")
        (field (name "CASE CODE (IMPERIAL)") "0402")
        (field (name "TOLERANCE") "5%")
        (field (name "RESISTANCE") "0R")
      )
      (libsource (lib "Electronic Devices_LIB") (part "RES_0R_5%_100mW_0402"))
    )
    (comp (ref "R168")
      (value "ERJ-2GEJ103X")
      (footprint "RES_0402_RESC1005X04N")
      (description "Res Thick Film 0402 10K Ohm 5% 1/10W ±200ppm/°C Molded SMD Punched Carrier T/R")
      (fields
        (field (name "MANUFACTURER") "Panasonic")
        (field (name "TOLERANCE") "5%")
        (field (name "RESISTANCE") "10K")
        (field (name "CASE/PACKAGE") "0402")
      )
      (libsource (lib "Electronic Devices_LIB") (part "RES_10K_5%_100mW_0402"))
    )
    (comp (ref "R169")
      (value "ERJ-2RKF4702X")
      (footprint "RES_0402_RESC1005X04N")
      (description "Res Thick Film 0402 47K Ohm 1% 0.1W ±100ppm/°C Molded SMD Punched Carrier T/R")
      (fields
        (field (name "MANUFACTURER") "Panasonic")
        (field (name "TOLERANCE") "1%")
        (field (name "RESISTANCE") "47K")
        (field (name "CASE/PACKAGE") "0402")
      )
      (libsource (lib "Electronic Devices_LIB") (part "RES_47K_1%_100MW_0402"))
    )
    (comp (ref "R170")
      (value "ERJ-2GE0R00X")
      (footprint "RES_0402_RESC1005X04N")
      (description "SMD Chip Resistor, Jumper, 0 ohm, 100 mW, 0402 [1005 Metric], Thick Film, General Purpose")
      (fields
        (field (name "MANUFACTURER") "Panasonic")
        (field (name "CASE CODE (IMPERIAL)") "0402")
        (field (name "TOLERANCE") "5%")
        (field (name "RESISTANCE") "0R")
      )
      (libsource (lib "Electronic Devices_LIB") (part "RES_0R_5%_100mW_0402"))
    )
    (comp (ref "TP45")
      (value "NO COMPONENT")
      (footprint "TP_PAD_0.5MM_SMD_ROUND")
      (description "Test Point, SMD pad, round, 1.5mm, 1.6mm, 3mm diameter")
      (libsource (lib "Electronic Devices_LIB") (part "TP_PAD_SMD_SMALL"))
    )
    (comp (ref "TP46")
      (value "NO COMPONENT")
      (footprint "TP_PAD_0.5MM_SMD_ROUND")
      (description "Test Point, SMD pad, round, 1.5mm, 1.6mm, 3mm diameter")
      (libsource (lib "Electronic Devices_LIB") (part "TP_PAD_SMD_SMALL"))
    )
    (comp (ref "U10")
      (value "NTS0104BQ,115")
      (footprint "QFN50P300X250X100-15N")
      (description "Voltage Level Translator Bidirectional 1 Circuit 4 Channel 50Mbps 14-DHVQFN (2.5x3)")
      (fields (field (name "MANUFACTURER") "NXP Semiconductors"))
      (libsource (lib "Electronic Devices_LIB") (part "IC_LEVEL_TRASLATE_4CH_NTS0104BQ,115"))
    )
    (comp (ref "U11")
      (value "CBTU02043HEJ")
      (footprint "IC_SW_TYPEC_CBTU02044HEJ")
      (description "USB 3.1 Gen 1 Type C switch / TAPE + REEL REEL 13\" Q1 NDP RoHS Compliant: Yes")
      (fields (field (name "MANUFACTURER") "NXP Semiconductors"))
      (libsource (lib "Electronic Devices_LIB") (part "IC_SWITCH_TYPEC_CBTU02043HEJ"))
    )
    (comp (ref "U12")
      (value "9FGV0241AKILF")
      (footprint "QFN50P400X400X100-25N-D")
      (description "Dual Output 1.8 V Very Low Power PCIE GEN1/2/3 Clock Generator - VFQFPN-24")
      (fields (field (name "MANUFACTURER") "Renesas"))
      (libsource (lib "Electronic Devices_LIB") (part "IC_CLOCK_PCIE_100MHZ_9FGV0241AKILF"))
    )
    (comp (ref "U13")
      (value "CBTU02043HEJ")
      (footprint "IC_SW_TYPEC_CBTU02044HEJ")
      (description "USB 3.1 Gen 1 Type C switch / TAPE + REEL REEL 13\" Q1 NDP RoHS Compliant: Yes")
      (fields (field (name "MANUFACTURER") "NXP Semiconductors"))
      (libsource (lib "Electronic Devices_LIB") (part "IC_SWITCH_TYPEC_CBTU02043HEJ"))
    )
    (comp (ref "U14")
      (value "74LVC1G04GW,125")
      (footprint "SOT65P210X110-5N")
      (description "74LVC Series 5.5 V Surface Mount Single Inverting Buffer - TSSOP-5")
      (fields (field (name "MANUFACTURER") "Nexperia"))
      (libsource (lib "Electronic Devices_LIB") (part "IC_INVERTER_1CH_74LVC1G04GW,125"))
    )
    (comp (ref "U15")
      (value "74LVC1G38GW,125")
      (footprint "SOT65P212X110-5N")
      (description "IC GATE NAND 1CH 2-INP 5-TSSOP")
      (fields (field (name "MANUFACTURER") "Nexperia"))
      (libsource (lib "Electronic Devices_LIB") (part "IC_GATE_NAND_1CH_74LVC1G38GW,125"))
    )
    (comp (ref "U16")
      (value "SN74AVC1T45DBVR")
      (footprint "SOT95P280X145-6N")
      (description "1.2V~3.6V 1 1 1.2V~3.6V 500Mbps SOT-23-6 Translators / Level Shifters ROHS")
      (fields (field (name "MANUFACTURER") "Texas Instruments"))
      (libsource (lib "Electronic Devices_LIB") (part "IC_LEVEL_TRANSLATOR_SN74AVC1T45DBVR"))
    )
    (comp (ref "Y4")
      (value "ASH7KW-32.768kHz-L-T")
      (footprint "CRYSTAL_32.768KHZ_ASH7KW32768kHzLT")
      (description "OSC XO 32.768KHZ CMOS SMD")
      (fields (field (name "MANUFACTURER") "Abracon") (field (name "FREQUENCY") "32.768KHz"))
      (libsource (lib "Electronic Devices_LIB") (part "CRYSTAL_ABRACON_32.768KHZ"))
    )
    (comp (ref "Y5")
      (value "ECS-250-18-33-JTM-TR")
      (footprint "CRYSTAL_ECS-250-18-33-JTM-TR")
      (description "Crystal 25MHz ±20ppm (Tol) ±20ppm (Stability) 18pF FUND 40Ohm 4-Pin Mini-CSMD T/R")
      (fields (field (name "MANUFACTURER") "ECS International") (field (name "FREQUENCY") "25MHz"))
      (libsource (lib "Electronic Devices_LIB") (part "CRYSTAL_ECS_25MHZ_ECS-250-18-33-JTM-TR"))
    )
  )
  (nets
    (net (code "6") (name "/BT_DIS_B") (class "Default")
      (node (ref "J13") (pin "54") (pinfunction "W_DISABLE2_54") (pintype "passive"))
    )
    (net (code "7") (name "/BT_OSC_32KHZ") (class "Default")
      (node (ref "J13") (pin "50") (pinfunction "SUSCLK_50") (pintype "passive"))
      (node (ref "Y4") (pin "1") (pinfunction "OUTPUT_1") (pintype "passive"))
    )
    (net (code "8") (name "/BT_UART_WAKE_B") (class "Default")
      (node (ref "J13") (pin "20") (pinfunction "UART_WAKE_20") (pintype "passive"))
    )
    (net (code "9") (name "/I2C1_SCL") (class "Default")
      (node (ref "R149") (pin "1") (pinfunction "1_1") (pintype "passive"))
      (node (ref "U10") (pin "2") (pinfunction "A1_2") (pintype "passive"))
      (node (ref "U12") (pin "8") (pinfunction "SCLK_3.3_8") (pintype "passive"))
    )
    (net (code "10") (name "/I2C1_SDA") (class "Default")
      (node (ref "R148") (pin "1") (pinfunction "1_1") (pintype "passive"))
      (node (ref "U10") (pin "3") (pinfunction "A2_3") (pintype "passive"))
      (node (ref "U12") (pin "9") (pinfunction "SDATA_3.3_9") (pintype "passive"))
    )
    (net (code "11") (name "/I2C3_SCL") (class "Default")
      (node (ref "J13") (pin "60") (pinfunction "I2C_CLK_60") (pintype "passive"))
      (node (ref "U10") (pin "13") (pinfunction "B1_13") (pintype "passive"))
    )
    (net (code "12") (name "/I2C3_SDA") (class "Default")
      (node (ref "J13") (pin "58") (pinfunction "I2C_DATA_58") (pintype "passive"))
      (node (ref "U10") (pin "12") (pinfunction "B2_12") (pintype "passive"))
    )
    (net (code "13") (name "/LED1") (class "Default")
      (node (ref "D10") (pin "1") (pinfunction "C_1") (pintype "passive"))
      (node (ref "J13") (pin "6") (pinfunction "LED1_6") (pintype "passive"))
    )
    (net (code "14") (name "/LED2") (class "Default")
      (node (ref "D11") (pin "1") (pinfunction "C_1") (pintype "passive"))
      (node (ref "J13") (pin "16") (pinfunction "LED2_16") (pintype "passive"))
    )
    (net (code "15") (name "/M.2_PCIE0_RX_N") (class "Default")
      (node (ref "J13") (pin "43") (pinfunction "PER_N0_43") (pintype "passive"))
      (node (ref "R152") (pin "2") (pinfunction "2_2") (pintype "passive"))
    )
    (net (code "16") (name "/M.2_PCIE0_RX_P") (class "Default")
      (node (ref "J13") (pin "41") (pinfunction "PER_P0_41") (pintype "passive"))
      (node (ref "R151") (pin "2") (pinfunction "2_2") (pintype "passive"))
    )
    (net (code "17") (name "/M.2_PCIE0_TX_N") (class "Default")
      (node (ref "C283") (pin "1") (pinfunction "1_1") (pintype "passive"))
      (node (ref "J13") (pin "37") (pinfunction "PET_N0_37") (pintype "passive"))
    )
    (net (code "18") (name "/M.2_PCIE0_TX_P") (class "Default")
      (node (ref "C282") (pin "1") (pinfunction "1_1") (pintype "passive"))
      (node (ref "J13") (pin "35") (pinfunction "PET_P0_35") (pintype "passive"))
    )
    (net (code "19") (name "/M.2_SAI0_RXC") (class "Default")
      (node (ref "R139") (pin "2") (pinfunction "2_2") (pintype "passive"))
      (node (ref "TP45") (pin "1") (pinfunction "1_1") (pintype "passive"))
    )
    (net (code "20") (name "/M.2_SAI0_RXD") (class "Default")
      (node (ref "J13") (pin "12") (pinfunction "I2S_SD_IN_12") (pintype "passive"))
      (node (ref "R138") (pin "2") (pinfunction "2_2") (pintype "passive"))
    )
    (net (code "21") (name "/M.2_SAI0_TXC") (class "Default")
      (node (ref "J13") (pin "8") (pinfunction "I2S_SCK_8") (pintype "passive"))
      (node (ref "R140") (pin "2") (pinfunction "2_2") (pintype "passive"))
    )
    (net (code "22") (name "/M.2_SAI0_TXD") (class "Default")
      (node (ref "J13") (pin "14") (pinfunction "I2S_SD_OUT_14") (pintype "passive"))
      (node (ref "R141") (pin "2") (pinfunction "2_2") (pintype "passive"))
    )
    (net (code "23") (name "/M.2_SAI0_TXFS") (class "Default")
      (node (ref "J13") (pin "10") (pinfunction "I2S_WS_10") (pintype "passive"))
      (node (ref "R142") (pin "2") (pinfunction "2_2") (pintype "passive"))
    )
    (net (code "24") (name "/M.2_USB_DN") (class "Default")
      (node (ref "J13") (pin "5") (pinfunction "USB_D-_5") (pintype "passive+no_connect"))
    )
    (net (code "25") (name "/M.2_USB_DP") (class "Default")
      (node (ref "J13") (pin "3") (pinfunction "USB_D+_3") (pintype "passive+no_connect"))
    )
    (net (code "26") (name "/M.2_WIFI_EN") (class "Default")
      (node (ref "J13") (pin "23") (pinfunction "SDIO_RST_23") (pintype "passive"))
      (node (ref "R146") (pin "1") (pinfunction "1_1") (pintype "passive"))
      (node (ref "U10") (pin "5") (pinfunction "A4_5") (pintype "passive"))
    )
    (net (code "27") (name "/M.2_WIFI_WAKE_B") (class "Default")
      (node (ref "J13") (pin "21") (pinfunction "SDIO_WAKE_21") (pintype "passive"))
      (node (ref "R147") (pin "1") (pinfunction "1_1") (pintype "passive"))
      (node (ref "U10") (pin "4") (pinfunction "A3_4") (pintype "passive"))
    )
    (net (code "28") (name "/M2_CLKREQ_B") (class "Default")
      (node (ref "R155") (pin "1") (pinfunction "1_1") (pintype "passive"))
      (node (ref "R169") (pin "1") (pinfunction "1_1") (pintype "passive"))
      (node (ref "U15") (pin "2") (pinfunction "B_2") (pintype "passive"))
    )
    (net (code "29") (name "/MICRO_REFCLK_N") (class "Default")
      (node (ref "U11") (pin "6") (pinfunction "C0_N_6") (pintype "passive"))
      (node (ref "U13") (pin "6") (pinfunction "C0_N_6") (pintype "passive"))
    )
    (net (code "30") (name "/MICRO_REFCLK_P") (class "Default")
      (node (ref "U11") (pin "5") (pinfunction "C0_P_5") (pintype "passive"))
      (node (ref "U13") (pin "5") (pinfunction "C0_P_5") (pintype "passive"))
    )
    (net (code "31") (name "/PCIE0_RX_N") (class "Default")
      (node (ref "R152") (pin "1") (pinfunction "1_1") (pintype "passive"))
    )
    (net (code "32") (name "/PCIE0_RX_P") (class "Default")
      (node (ref "R151") (pin "1") (pinfunction "1_1") (pintype "passive"))
    )
    (net (code "33") (name "/PCIE0_TX_N") (class "Default")
      (node (ref "C283") (pin "2") (pinfunction "2_2") (pintype "passive"))
    )
    (net (code "34") (name "/PCIE0_TX_P") (class "Default")
      (node (ref "C282") (pin "2") (pinfunction "2_2") (pintype "passive"))
    )
    (net (code "35") (name "/PCIE_CLK_SEL") (class "Default")
      (node (ref "R154") (pin "2") (pinfunction "2_2") (pintype "passive"))
      (node (ref "U11") (pin "12") (pinfunction "SEL_12") (pintype "passive"))
      (node (ref "U13") (pin "12") (pinfunction "SEL_12") (pintype "passive"))
    )
    (net (code "36") (name "/PCIE_CONN_REFCLK_N") (class "Default")
      (node (ref "J13") (pin "49") (pinfunction "REFCLK_N0_49") (pintype "passive"))
      (node (ref "R157") (pin "2") (pinfunction "2_2") (pintype "passive"))
      (node (ref "U13") (pin "9") (pinfunction "A0_N_9") (pintype "passive"))
    )
    (net (code "37") (name "/PCIE_CONN_REFCLK_P") (class "Default")
      (node (ref "J13") (pin "47") (pinfunction "REFCLK_P0_47") (pintype "passive"))
      (node (ref "R156") (pin "2") (pinfunction "2_2") (pintype "passive"))
      (node (ref "U13") (pin "10") (pinfunction "A0_P_10") (pintype "passive"))
    )
    (net (code "38") (name "/PCIE_CTRL_CLKREQ_B") (class "Default")
      (node (ref "R168") (pin "1") (pinfunction "1_1") (pintype "passive"))
      (node (ref "U15") (pin "1") (pinfunction "A_1") (pintype "passive"))
    )
    (net (code "39") (name "/PCIE_CTRL_PERST_B") (class "Default")
      (node (ref "R153") (pin "1") (pinfunction "1_1") (pintype "passive"))
    )
    (net (code "40") (name "/PCIE_CTRL_WAKE_B") (class "Default")
      (node (ref "J13") (pin "55") (pinfunction "PEWAKE0_55") (pintype "passive"))
      (node (ref "R150") (pin "1") (pinfunction "1_1") (pintype "passive"))
    )
    (net (code "41") (name "/PCIE_REF_CLK_N") (class "Default")
      (node (ref "R137") (pin "2") (pinfunction "2_2") (pintype "passive"))
      (node (ref "U11") (pin "9") (pinfunction "A0_N_9") (pintype "passive"))
    )
    (net (code "42") (name "/PCIE_REF_CLK_P") (class "Default")
      (node (ref "R136") (pin "2") (pinfunction "2_2") (pintype "passive"))
      (node (ref "U11") (pin "10") (pinfunction "A0_P_10") (pintype "passive"))
    )
    (net (code "43") (name "/PCI_CLKREQ") (class "Default")
      (node (ref "R163") (pin "2") (pinfunction "2_2") (pintype "passive"))
      (node (ref "R166") (pin "1") (pinfunction "1_1") (pintype "passive"))
      (node (ref "R167") (pin "1") (pinfunction "1_1") (pintype "passive"))
      (node (ref "R167") (pin "2") (pinfunction "2_2") (pintype "passive"))
      (node (ref "U12") (pin "22") (pinfunction "CKPWRGD_PD#_22") (pintype "passive"))
      (node (ref "U15") (pin "4") (pinfunction "Y_4") (pintype "passive"))
    )
    (net (code "44") (name "/PCI_XTAL_X1") (class "Default")
      (node (ref "C294") (pin "2") (pinfunction "2_2") (pintype "passive"))
      (node (ref "U12") (pin "1") (pinfunction "X1_25_1") (pintype "passive"))
      (node (ref "Y5") (pin "1") (pinfunction "IN_1") (pintype "passive"))
    )
    (net (code "45") (name "/PCI_XTAL_X2") (class "Default")
      (node (ref "R160") (pin "2") (pinfunction "2_2") (pintype "passive"))
      (node (ref "U12") (pin "2") (pinfunction "X2_2") (pintype "passive"))
    )
    (net (code "46") (name "/REFCLK1_N") (class "Default")
      (node (ref "R159") (pin "2") (pinfunction "2_2") (pintype "passive"))
      (node (ref "U11") (pin "7") (pinfunction "B0_N_7") (pintype "passive"))
    )
    (net (code "47") (name "/REFCLK1_P") (class "Default")
      (node (ref "R158") (pin "2") (pinfunction "2_2") (pintype "passive"))
      (node (ref "U11") (pin "8") (pinfunction "B0_P_8") (pintype "passive"))
    )
    (net (code "48") (name "/REFCLK2_N") (class "Default")
      (node (ref "R162") (pin "2") (pinfunction "2_2") (pintype "passive"))
      (node (ref "U13") (pin "7") (pinfunction "B0_N_7") (pintype "passive"))
    )
    (net (code "49") (name "/REFCLK2_P") (class "Default")
      (node (ref "R161") (pin "2") (pinfunction "2_2") (pintype "passive"))
      (node (ref "U13") (pin "8") (pinfunction "B0_P_8") (pintype "passive"))
    )
    (net (code "50") (name "/SPI0_CS0") (class "Default")
      (node (ref "R138") (pin "1") (pinfunction "1_1") (pintype "passive"))
    )
    (net (code "51") (name "/SPI0_CS1") (class "Default")
      (node (ref "R139") (pin "1") (pinfunction "1_1") (pintype "passive"))
    )
    (net (code "52") (name "/SPI0_SCK") (class "Default")
      (node (ref "R140") (pin "1") (pinfunction "1_1") (pintype "passive"))
    )
    (net (code "53") (name "/SPI0_SDI") (class "Default")
      (node (ref "R141") (pin "1") (pinfunction "1_1") (pintype "passive"))
    )
    (net (code "54") (name "/SPI0_SDO") (class "Default")
      (node (ref "R142") (pin "1") (pinfunction "1_1") (pintype "passive"))
    )
    (net (code "55") (name "/SS_CNTRL") (class "Default")
      (node (ref "U14") (pin "2") (pinfunction "A_2") (pintype "passive"))
    )
    (net (code "56") (name "/SS_CNTRL_B") (class "Default")
      (node (ref "U14") (pin "4") (pinfunction "Y_4") (pintype "passive"))
      (node (ref "U16") (pin "4") (pinfunction "B_4") (pintype "passive"))
    )
    (net (code "57") (name "/SS_EN_TRI") (class "Default")
      (node (ref "U12") (pin "23") (pinfunction "SS_EN_TRI_23") (pintype "passive"))
      (node (ref "U16") (pin "3") (pinfunction "A_3") (pintype "passive"))
    )
    (net (code "58") (name "/UART1_CTS_B") (class "Default")
      (node (ref "J13") (pin "34") (pinfunction "UART_CTS_34") (pintype "passive+no_connect"))
    )
    (net (code "59") (name "/UART1_RTS_B") (class "Default")
      (node (ref "J13") (pin "36") (pinfunction "UART_RTS_36") (pintype "passive+no_connect"))
    )
    (net (code "60") (name "/UART1_RX") (class "Default")
      (node (ref "J13") (pin "22") (pinfunction "UART_RXD_22") (pintype "passive+no_connect"))
    )
    (net (code "61") (name "/UART1_TX") (class "Default")
      (node (ref "J13") (pin "32") (pinfunction "UART_TXD_32") (pintype "passive+no_connect"))
    )
    (net (code "62") (name "/WIFI_DIS_B") (class "Default")
      (node (ref "J13") (pin "56") (pinfunction "W_DISABLE1_56") (pintype "passive"))
    )
    (net (code "63") (name "/WIFI_EN") (class "Default")
      (node (ref "U10") (pin "10") (pinfunction "B4_10") (pintype "passive"))
    )
    (net (code "64") (name "/WIFI_WAKE_B") (class "Default")
      (node (ref "U10") (pin "11") (pinfunction "B3_11") (pintype "passive"))
    )
    (net (code "65") (name "/XTAL2") (class "Default")
      (node (ref "C295") (pin "2") (pinfunction "2_2") (pintype "passive"))
      (node (ref "R160") (pin "1") (pinfunction "1_1") (pintype "passive"))
      (node (ref "Y5") (pin "3") (pinfunction "OUT_3") (pintype "passive"))
    )
    (net (code "71") (name "1V8") (class "Default")
      (node (ref "C280") (pin "2") (pinfunction "2_2") (pintype "passive"))
      (node (ref "C284") (pin "2") (pinfunction "2_2") (pintype "passive"))
      (node (ref "C285") (pin "2") (pinfunction "2_2") (pintype "passive"))
      (node (ref "C298") (pin "1") (pinfunction "1_1") (pintype "passive"))
      (node (ref "FB4") (pin "2") (pinfunction "2_2") (pintype "passive"))
      (node (ref "FB5") (pin "1") (pinfunction "1_1") (pintype "passive"))
      (node (ref "R145") (pin "2") (pinfunction "2_2") (pintype "passive"))
      (node (ref "R146") (pin "2") (pinfunction "2_2") (pintype "passive"))
      (node (ref "R147") (pin "2") (pinfunction "2_2") (pintype "passive"))
      (node (ref "R148") (pin "2") (pinfunction "2_2") (pintype "passive"))
      (node (ref "R149") (pin "2") (pinfunction "2_2") (pintype "passive"))
      (node (ref "R166") (pin "2") (pinfunction "2_2") (pintype "passive"))
      (node (ref "U10") (pin "1") (pinfunction "VCCA_1") (pintype "power_in"))
      (node (ref "U12") (pin "7") (pinfunction "VDDDIG1.8_7") (pintype "passive"))
      (node (ref "U16") (pin "1") (pinfunction "VCCA_1") (pintype "passive"))
    )
    (net (code "72") (name "3V3") (class "Default")
      (node (ref "C275") (pin "2") (pinfunction "2_2") (pintype "passive"))
      (node (ref "C276") (pin "2") (pinfunction "2_2") (pintype "passive"))
      (node (ref "C277") (pin "2") (pinfunction "2_2") (pintype "passive"))
      (node (ref "C278") (pin "2") (pinfunction "2_2") (pintype "passive"))
      (node (ref "C279") (pin "2") (pinfunction "2_2") (pintype "passive"))
      (node (ref "C281") (pin "2") (pinfunction "2_2") (pintype "passive"))
      (node (ref "C292") (pin "2") (pinfunction "2_2") (pintype "passive"))
      (node (ref "C293") (pin "2") (pinfunction "2_2") (pintype "passive"))
      (node (ref "C296") (pin "1") (pinfunction "1_1") (pintype "passive"))
      (node (ref "C297") (pin "1") (pinfunction "1_1") (pintype "passive"))
      (node (ref "C299") (pin "1") (pinfunction "1_1") (pintype "passive"))
      (node (ref "J13") (pin "2") (pinfunction "3V3_1_2") (pintype "passive"))
      (node (ref "J13") (pin "4") (pinfunction "3V3_2_4") (pintype "passive"))
      (node (ref "J13") (pin "72") (pinfunction "3V3_3_72") (pintype "passive"))
      (node (ref "J13") (pin "74") (pinfunction "3V3_4_74") (pintype "passive"))
      (node (ref "R143") (pin "2") (pinfunction "2_2") (pintype "passive"))
      (node (ref "R144") (pin "2") (pinfunction "2_2") (pintype "passive"))
      (node (ref "R150") (pin "2") (pinfunction "2_2") (pintype "passive"))
      (node (ref "R154") (pin "1") (pinfunction "1_1") (pintype "passive"))
      (node (ref "R168") (pin "2") (pinfunction "2_2") (pintype "passive"))
      (node (ref "R169") (pin "2") (pinfunction "2_2") (pintype "passive"))
      (node (ref "U10") (pin "14") (pinfunction "VCCB_14") (pintype "power_in"))
      (node (ref "U11") (pin "4") (pinfunction "VDD_4") (pintype "power_in"))
      (node (ref "U13") (pin "4") (pinfunction "VDD_4") (pintype "power_in"))
      (node (ref "U14") (pin "5") (pinfunction "VCC_5") (pintype "power_in"))
      (node (ref "U15") (pin "5") (pinfunction "VCC_5") (pintype "passive"))
      (node (ref "U16") (pin "6") (pinfunction "VCCB_6") (pintype "passive"))
      (node (ref "Y4") (pin "3") (pinfunction "OE_3") (pintype "passive"))
      (node (ref "Y4") (pin "4") (pinfunction "VDD_4") (pintype "passive"))
    )
    (net (code "73") (name "GND") (class "Default")
      (node (ref "C275") (pin "1") (pinfunction "1_1") (pintype "passive"))
      (node (ref "C276") (pin "1") (pinfunction "1_1") (pintype "passive"))
      (node (ref "C277") (pin "1") (pinfunction "1_1") (pintype "passive"))
      (node (ref "C278") (pin "1") (pinfunction "1_1") (pintype "passive"))
      (node (ref "C279") (pin "1") (pinfunction "1_1") (pintype "passive"))
      (node (ref "C280") (pin "1") (pinfunction "1_1") (pintype "passive"))
      (node (ref "C281") (pin "1") (pinfunction "1_1") (pintype "passive"))
      (node (ref "C284") (pin "1") (pinfunction "1_1") (pintype "passive"))
      (node (ref "C285") (pin "1") (pinfunction "1_1") (pintype "passive"))
      (node (ref "C286") (pin "1") (pinfunction "1_1") (pintype "passive"))
      (node (ref "C287") (pin "1") (pinfunction "1_1") (pintype "passive"))
      (node (ref "C288") (pin "1") (pinfunction "1_1") (pintype "passive"))
      (node (ref "C289") (pin "1") (pinfunction "1_1") (pintype "passive"))
      (node (ref "C290") (pin "1") (pinfunction "1_1") (pintype "passive"))
      (node (ref "C291") (pin "1") (pinfunction "1_1") (pintype "passive"))
      (node (ref "C292") (pin "1") (pinfunction "1_1") (pintype "passive"))
      (node (ref "C293") (pin "1") (pinfunction "1_1") (pintype "passive"))
      (node (ref "C294") (pin "1") (pinfunction "1_1") (pintype "passive"))
      (node (ref "C295") (pin "1") (pinfunction "1_1") (pintype "passive"))
      (node (ref "C296") (pin "2") (pinfunction "2_2") (pintype "passive"))
      (node (ref "C297") (pin "2") (pinfunction "2_2") (pintype "passive"))
      (node (ref "C298") (pin "2") (pinfunction "2_2") (pintype "passive"))
      (node (ref "C299") (pin "2") (pinfunction "2_2") (pintype "passive"))
      (node (ref "J13") (pin "1") (pinfunction "GND1_1") (pintype "passive"))
      (node (ref "J13") (pin "18") (pinfunction "GND3_18") (pintype "passive"))
      (node (ref "J13") (pin "33") (pinfunction "GND5_33") (pintype "passive"))
      (node (ref "J13") (pin "39") (pinfunction "GND4_39") (pintype "passive"))
      (node (ref "J13") (pin "45") (pinfunction "GND6_45") (pintype "passive"))
      (node (ref "J13") (pin "51") (pinfunction "GND7_51") (pintype "passive"))
      (node (ref "J13") (pin "57") (pinfunction "GND8_57") (pintype "passive"))
      (node (ref "J13") (pin "63") (pinfunction "GND9_63") (pintype "passive"))
      (node (ref "J13") (pin "69") (pinfunction "GND10_69") (pintype "passive"))
      (node (ref "J13") (pin "7") (pinfunction "GND2_7") (pintype "passive"))
      (node (ref "J13") (pin "75") (pinfunction "GND11_75") (pintype "passive"))
      (node (ref "J13") (pin "S1") (pinfunction "SHIELD_S1") (pintype "passive"))
      (node (ref "J13") (pin "S2") (pinfunction "SHIELD_S2") (pintype "passive"))
      (node (ref "R156") (pin "1") (pinfunction "1_1") (pintype "passive"))
      (node (ref "R157") (pin "1") (pinfunction "1_1") (pintype "passive"))
      (node (ref "R163") (pin "1") (pinfunction "1_1") (pintype "passive"))
      (node (ref "R164") (pin "1") (pinfunction "1_1") (pintype "passive"))
      (node (ref "R165") (pin "1") (pinfunction "1_1") (pintype "passive"))
      (node (ref "R170") (pin "2") (pinfunction "2_2") (pintype "passive"))
      (node (ref "U10") (pin "6") (pinfunction "NC_6") (pintype "passive"))
      (node (ref "U10") (pin "9") (pinfunction "NC_9") (pintype "passive"))
      (node (ref "U11") (pin "11") (pinfunction "VSS_11") (pintype "power_in"))
      (node (ref "U11") (pin "13") (pinfunction "A1_P_13") (pintype "passive"))
      (node (ref "U11") (pin "14") (pinfunction "A1_N_14") (pintype "passive"))
      (node (ref "U11") (pin "17") (pinfunction "EPAD_17") (pintype "power_in"))
      (node (ref "U11") (pin "3") (pinfunction "XSD_3") (pintype "passive"))
      (node (ref "U12") (pin "10") (pinfunction "GND_1_10") (pintype "passive"))
      (node (ref "U12") (pin "15") (pinfunction "GNDA_15") (pintype "passive"))
      (node (ref "U12") (pin "21") (pinfunction "GND_2_21") (pintype "passive"))
      (node (ref "U12") (pin "24") (pinfunction "GNDXTAL_24") (pintype "passive"))
      (node (ref "U12") (pin "25") (pinfunction "GND_3_25") (pintype "passive"))
      (node (ref "U12") (pin "5") (pinfunction "GNDREF_5") (pintype "passive"))
      (node (ref "U12") (pin "6") (pinfunction "GNDDIG_6") (pintype "passive"))
      (node (ref "U13") (pin "11") (pinfunction "VSS_11") (pintype "power_in"))
      (node (ref "U13") (pin "13") (pinfunction "A1_P_13") (pintype "passive"))
      (node (ref "U13") (pin "14") (pinfunction "A1_N_14") (pintype "passive"))
      (node (ref "U13") (pin "17") (pinfunction "EPAD_17") (pintype "power_in"))
      (node (ref "U13") (pin "3") (pinfunction "XSD_3") (pintype "passive"))
      (node (ref "U14") (pin "1") (pinfunction "NC_1") (pintype "passive"))
      (node (ref "U14") (pin "3") (pinfunction "GND_3") (pintype "power_in"))
      (node (ref "U15") (pin "3") (pinfunction "GND_3") (pintype "passive"))
      (node (ref "U16") (pin "2") (pinfunction "GND_2") (pintype "passive"))
      (node (ref "Y4") (pin "2") (pinfunction "GND_2") (pintype "passive"))
      (node (ref "Y5") (pin "2") (pinfunction "2_2") (pintype "passive"))
      (node (ref "Y5") (pin "4") (pinfunction "4_4") (pintype "passive"))
    )
    (net (code "74") (name "Net-(D10-A)") (class "Default")
      (node (ref "D10") (pin "2") (pinfunction "A_2") (pintype "passive"))
      (node (ref "R143") (pin "1") (pinfunction "1_1") (pintype "passive"))
    )
    (net (code "75") (name "Net-(D11-A)") (class "Default")
      (node (ref "D11") (pin "2") (pinfunction "A_2") (pintype "passive"))
      (node (ref "R144") (pin "1") (pinfunction "1_1") (pintype "passive"))
    )
    (net (code "76") (name "Net-(J13-CLKREQ0)") (class "Default")
      (node (ref "J13") (pin "53") (pinfunction "CLKREQ0_53") (pintype "passive"))
      (node (ref "R155") (pin "2") (pinfunction "2_2") (pintype "passive"))
    )
    (net (code "77") (name "Net-(J13-PERST0)") (class "Default")
      (node (ref "J13") (pin "52") (pinfunction "PERST0_52") (pintype "passive"))
      (node (ref "R153") (pin "2") (pinfunction "2_2") (pintype "passive"))
    )
    (net (code "78") (name "Net-(U10-OE)") (class "Default")
      (node (ref "R145") (pin "1") (pinfunction "1_1") (pintype "passive"))
      (node (ref "U10") (pin "8") (pinfunction "OE_8") (pintype "passive"))
    )
    (net (code "79") (name "Net-(U12-DIF0#)") (class "Default")
      (node (ref "R162") (pin "1") (pinfunction "1_1") (pintype "passive"))
      (node (ref "U12") (pin "14") (pinfunction "DIF0#_14") (pintype "passive"))
    )
    (net (code "80") (name "Net-(U12-DIF0)") (class "Default")
      (node (ref "R161") (pin "1") (pinfunction "1_1") (pintype "passive"))
      (node (ref "U12") (pin "13") (pinfunction "DIF0_13") (pintype "passive"))
    )
    (net (code "81") (name "Net-(U12-DIF1#)") (class "Default")
      (node (ref "R159") (pin "1") (pinfunction "1_1") (pintype "passive"))
      (node (ref "U12") (pin "18") (pinfunction "DIF1#_18") (pintype "passive"))
    )
    (net (code "82") (name "Net-(U12-DIF1)") (class "Default")
      (node (ref "R158") (pin "1") (pinfunction "1_1") (pintype "passive"))
      (node (ref "U12") (pin "17") (pinfunction "DIF1_17") (pintype "passive"))
    )
    (net (code "83") (name "Net-(U12-OE0#)") (class "Default")
      (node (ref "R164") (pin "2") (pinfunction "2_2") (pintype "passive"))
      (node (ref "U12") (pin "12") (pinfunction "OE0#_12") (pintype "passive"))
    )
    (net (code "84") (name "Net-(U12-OE1#)") (class "Default")
      (node (ref "R165") (pin "2") (pinfunction "2_2") (pintype "passive"))
      (node (ref "U12") (pin "19") (pinfunction "OE1#_19") (pintype "passive"))
    )
    (net (code "85") (name "Net-(U12-SADR{slash}REF1.8)") (class "Default")
      (node (ref "TP46") (pin "1") (pinfunction "1_1") (pintype "passive"))
      (node (ref "U12") (pin "4") (pinfunction "SADR/REF1.8_4") (pintype "passive"))
    )
    (net (code "86") (name "Net-(U12-VDD1.8_1)") (class "Default")
      (node (ref "C289") (pin "2") (pinfunction "2_2") (pintype "passive"))
      (node (ref "C290") (pin "2") (pinfunction "2_2") (pintype "passive"))
      (node (ref "C291") (pin "2") (pinfunction "2_2") (pintype "passive"))
      (node (ref "FB5") (pin "2") (pinfunction "2_2") (pintype "passive"))
      (node (ref "U12") (pin "11") (pinfunction "VDD1.8_1_11") (pintype "passive"))
      (node (ref "U12") (pin "20") (pinfunction "VDD1.8_2_20") (pintype "passive"))
    )
    (net (code "87") (name "Net-(U12-VDDA1.8)") (class "Default")
      (node (ref "C286") (pin "2") (pinfunction "2_2") (pintype "passive"))
      (node (ref "C287") (pin "2") (pinfunction "2_2") (pintype "passive"))
      (node (ref "C288") (pin "2") (pinfunction "2_2") (pintype "passive"))
      (node (ref "FB4") (pin "1") (pinfunction "1_1") (pintype "passive"))
      (node (ref "U12") (pin "16") (pinfunction "VDDA1.8_16") (pintype "passive"))
      (node (ref "U12") (pin "3") (pinfunction "VDDXTAL1.8_3") (pintype "passive"))
    )
    (net (code "88") (name "Net-(U16-DIR)") (class "Default")
      (node (ref "R170") (pin "1") (pinfunction "1_1") (pintype "passive"))
      (node (ref "U16") (pin "5") (pinfunction "DIR_5") (pintype "passive"))
    )
    (net (code "89") (name "unconnected-(J13-ALERT-Pad62)") (class "Default")
      (node (ref "J13") (pin "62") (pinfunction "ALERT_62") (pintype "passive+no_connect"))
    )
    (net (code "90") (name "unconnected-(J13-CLKREQ1-Pad68)") (class "Default")
      (node (ref "J13") (pin "68") (pinfunction "CLKREQ1_68") (pintype "passive+no_connect"))
    )
    (net (code "91") (name "unconnected-(J13-COEX1-Pad48)") (class "Default")
      (node (ref "J13") (pin "48") (pinfunction "COEX1_48") (pintype "passive+no_connect"))
    )
    (net (code "92") (name "unconnected-(J13-COEX2-Pad46)") (class "Default")
      (node (ref "J13") (pin "46") (pinfunction "COEX2_46") (pintype "passive+no_connect"))
    )
    (net (code "93") (name "unconnected-(J13-COEX3-Pad44)") (class "Default")
      (node (ref "J13") (pin "44") (pinfunction "COEX3_44") (pintype "passive+no_connect"))
    )
    (net (code "94") (name "unconnected-(J13-PERST1-Pad66)") (class "Default")
      (node (ref "J13") (pin "66") (pinfunction "PERST1_66") (pintype "passive+no_connect"))
    )
    (net (code "95") (name "unconnected-(J13-PER_N1-Pad67)") (class "Default")
      (node (ref "J13") (pin "67") (pinfunction "PER_N1_67") (pintype "passive+no_connect"))
    )
    (net (code "96") (name "unconnected-(J13-PER_P1-Pad65)") (class "Default")
      (node (ref "J13") (pin "65") (pinfunction "PER_P1_65") (pintype "passive+no_connect"))
    )
    (net (code "97") (name "unconnected-(J13-PET_N1-Pad61)") (class "Default")
      (node (ref "J13") (pin "61") (pinfunction "PET_N1_61") (pintype "passive+no_connect"))
    )
    (net (code "98") (name "unconnected-(J13-PET_P1-Pad59)") (class "Default")
      (node (ref "J13") (pin "59") (pinfunction "PET_P1_59") (pintype "passive+no_connect"))
    )
    (net (code "99") (name "unconnected-(J13-PEWAKE1-Pad70)") (class "Default")
      (node (ref "J13") (pin "70") (pinfunction "PEWAKE1_70") (pintype "passive+no_connect"))
    )
    (net (code "100") (name "unconnected-(J13-REFCLK_N1-Pad73)") (class "Default")
      (node (ref "J13") (pin "73") (pinfunction "REFCLK_N1_73") (pintype "passive+no_connect"))
    )
    (net (code "101") (name "unconnected-(J13-REFCLK_P1-Pad71)") (class "Default")
      (node (ref "J13") (pin "71") (pinfunction "REFCLK_P1_71") (pintype "passive+no_connect"))
    )
    (net (code "102") (name "unconnected-(J13-RESERVED-Pad64)") (class "Default")
      (node (ref "J13") (pin "64") (pinfunction "RESERVED_64") (pintype "passive+no_connect"))
    )
    (net (code "103") (name "unconnected-(J13-SDIO_CLK-Pad9)") (class "Default")
      (node (ref "J13") (pin "9") (pinfunction "SDIO_CLK_9") (pintype "passive+no_connect"))
    )
    (net (code "104") (name "unconnected-(J13-SDIO_CMD-Pad11)") (class "Default")
      (node (ref "J13") (pin "11") (pinfunction "SDIO_CMD_11") (pintype "passive+no_connect"))
    )
    (net (code "105") (name "unconnected-(J13-SDIO_DATA0-Pad13)") (class "Default")
      (node (ref "J13") (pin "13") (pinfunction "SDIO_DATA0_13") (pintype "passive+no_connect"))
    )
    (net (code "106") (name "unconnected-(J13-SDIO_DATA1-Pad15)") (class "Default")
      (node (ref "J13") (pin "15") (pinfunction "SDIO_DATA1_15") (pintype "passive+no_connect"))
    )
    (net (code "107") (name "unconnected-(J13-SDIO_DATA2-Pad17)") (class "Default")
      (node (ref "J13") (pin "17") (pinfunction "SDIO_DATA2_17") (pintype "passive+no_connect"))
    )
    (net (code "108") (name "unconnected-(J13-SDIO_DATA3-Pad19)") (class "Default")
      (node (ref "J13") (pin "19") (pinfunction "SDIO_DATA3_19") (pintype "passive+no_connect"))
    )
    (net (code "109") (name "unconnected-(J13-VEN_DEF1-Pad38)") (class "Default")
      (node (ref "J13") (pin "38") (pinfunction "VEN_DEF1_38") (pintype "passive+no_connect"))
    )
    (net (code "110") (name "unconnected-(J13-VEN_DEF2-Pad40)") (class "Default")
      (node (ref "J13") (pin "40") (pinfunction "VEN_DEF2_40") (pintype "passive+no_connect"))
    )
    (net (code "111") (name "unconnected-(J13-VEN_DEF3-Pad42)") (class "Default")
      (node (ref "J13") (pin "42") (pinfunction "VEN_DEF3_42") (pintype "passive+no_connect"))
    )
    (net (code "112") (name "unconnected-(R136-Pad1)") (class "Default")
      (node (ref "R136") (pin "1") (pinfunction "1_1") (pintype "passive"))
    )
    (net (code "113") (name "unconnected-(R137-Pad1)") (class "Default")
      (node (ref "R137") (pin "1") (pinfunction "1_1") (pintype "passive"))
    )
    (net (code "114") (name "unconnected-(U10-EP-Pad15)") (class "Default")
      (node (ref "U10") (pin "15") (pinfunction "EP_15") (pintype "passive+no_connect"))
    )
    (net (code "115") (name "unconnected-(U10-GND-Pad7)") (class "Default")
      (node (ref "U10") (pin "7") (pinfunction "GND_7") (pintype "power_in+no_connect"))
    )
    (net (code "116") (name "unconnected-(U11-B1_N-Pad1)") (class "Default")
      (node (ref "U11") (pin "1") (pinfunction "B1_N_1") (pintype "passive+no_connect"))
    )
    (net (code "117") (name "unconnected-(U11-B1_P-Pad2)") (class "Default")
      (node (ref "U11") (pin "2") (pinfunction "B1_P_2") (pintype "passive+no_connect"))
    )
    (net (code "118") (name "unconnected-(U11-C1_N-Pad16)") (class "Default")
      (node (ref "U11") (pin "16") (pinfunction "C1_N_16") (pintype "passive+no_connect"))
    )
    (net (code "119") (name "unconnected-(U11-C1_P-Pad15)") (class "Default")
      (node (ref "U11") (pin "15") (pinfunction "C1_P_15") (pintype "passive+no_connect"))
    )
    (net (code "120") (name "unconnected-(U13-B1_N-Pad1)") (class "Default")
      (node (ref "U13") (pin "1") (pinfunction "B1_N_1") (pintype "passive+no_connect"))
    )
    (net (code "121") (name "unconnected-(U13-B1_P-Pad2)") (class "Default")
      (node (ref "U13") (pin "2") (pinfunction "B1_P_2") (pintype "passive+no_connect"))
    )
    (net (code "122") (name "unconnected-(U13-C1_N-Pad16)") (class "Default")
      (node (ref "U13") (pin "16") (pinfunction "C1_N_16") (pintype "passive+no_connect"))
    )
    (net (code "123") (name "unconnected-(U13-C1_P-Pad15)") (class "Default")
      (node (ref "U13") (pin "15") (pinfunction "C1_P_15") (pintype "passive+no_connect"))
    )
  )
)
